# Sheet2.net
KiCad netlist of a schematic drawn in Altium Designer
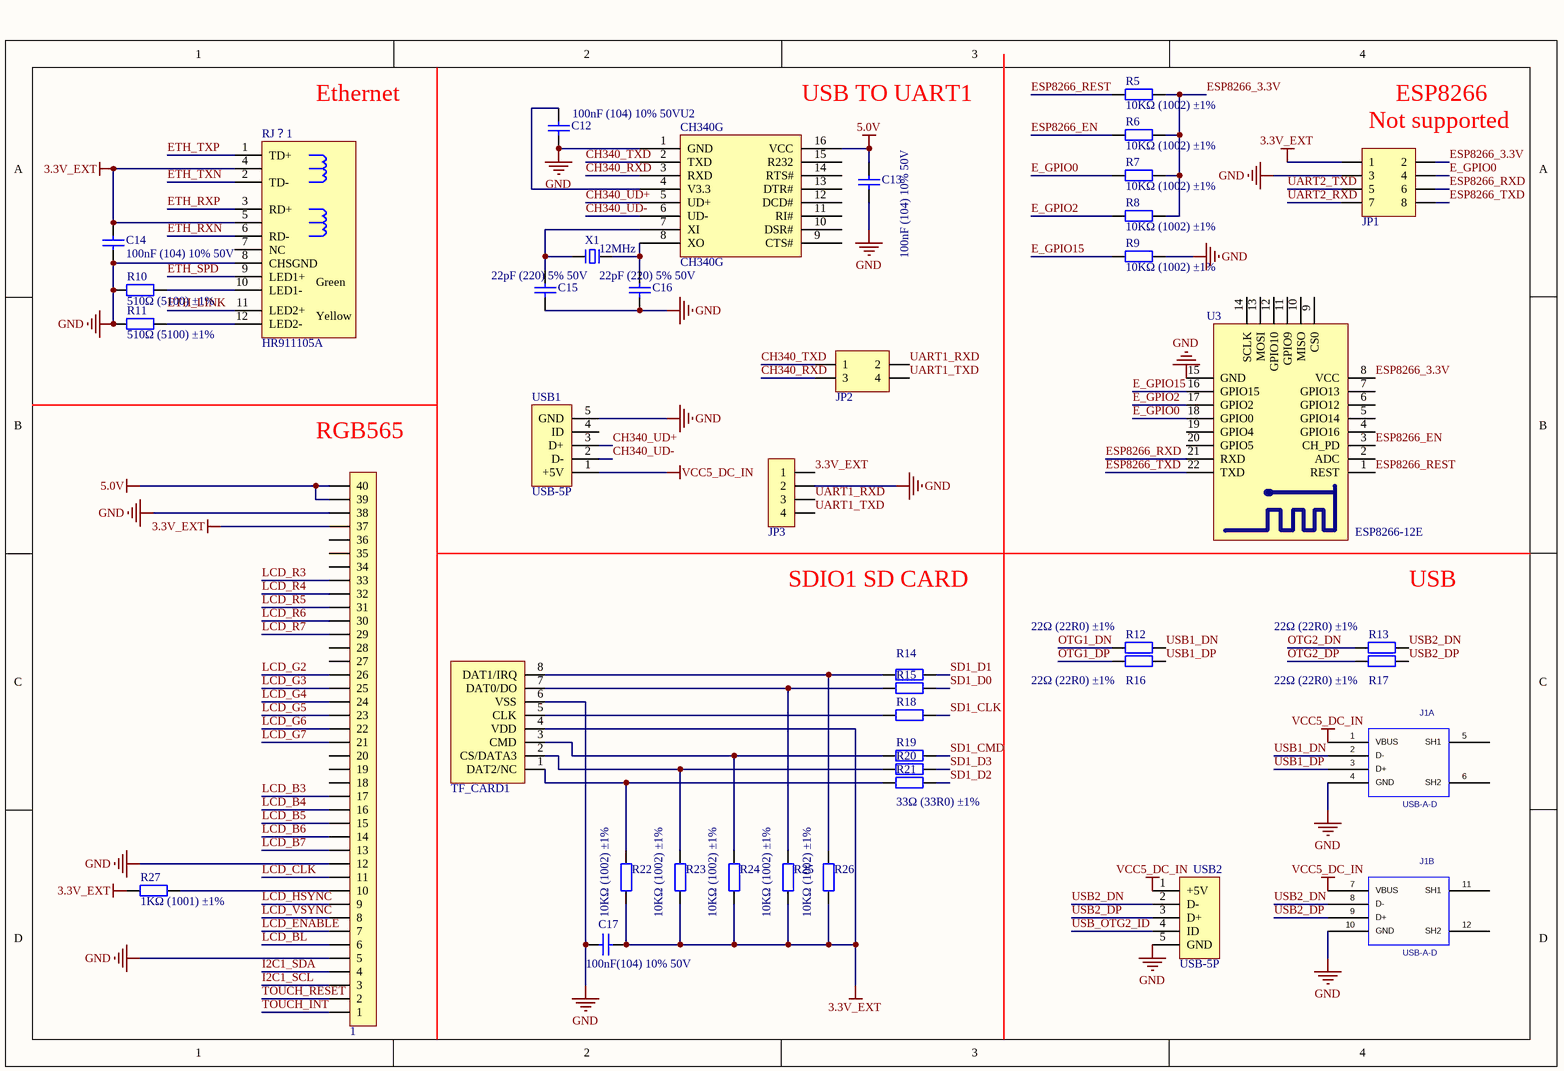
[diagram p0: Sheet2.SchDoc]

(export (version "E")
  (design (tool "Eeschema 10.0.6"))
  (components
    (comp (ref "1")
      (value "FPC1.0-40P")
      (footprint "FPC0.5 2H-S-W-40P")
      (description "FPC连接器")
      (fields (field (name "版权归属") "源创客"))
      (libsource (lib "FPC连接器") (part "FPC-40P"))
    )
    (comp (ref "C12")
      (value "100nF (104) 10% 50V")
      (footprint "0603_C")
      (description "贴片电容")
      (libsource (lib "Cap") (part "0603 100nF (104) 10% 50V"))
    )
    (comp (ref "C13")
      (value "100nF (104) 10% 50V")
      (footprint "0603_C")
      (description "贴片电容")
      (libsource (lib "Cap") (part "0603 100nF (104) 10% 50V"))
    )
    (comp (ref "C14")
      (value "100nF (104) 10% 50V")
      (footprint "0603_C")
      (description "贴片电容")
      (libsource (lib "Cap") (part "0603 100nF (104) 10% 50V"))
    )
    (comp (ref "C15")
      (value "22pF (220) 5% 50V")
      (footprint "0603_C")
      (description "贴片电容")
      (libsource (lib "Cap") (part "0805 22pF (220) 5% 50V"))
    )
    (comp (ref "C16")
      (value "22pF (220) 5% 50V")
      (footprint "0603_C")
      (description "贴片电容")
      (libsource (lib "Cap") (part "0805 22pF (220) 5% 50V"))
    )
    (comp (ref "C17")
      (value "100nF(104) 10% 50V")
      (footprint "0805_C")
      (description "贴片电容")
      (libsource (lib "Cap") (part "0805 100nF(104) 10% 50V"))
    )
    (comp (ref "J1")
      (value "USB-A-D")
      (footprint "USB-A-D")
      (fields (field (name "Comment") "USB-A-D_0"))
      (libsource (lib "IMXRT1052_MB_PRO") (part "USB-A-D_0"))
    )
    (comp (ref "JP1")
      (value "Header 4X2")
      (footprint "HDR-4X2")
      (description "4*2P接插件")
      (fields (field (name "版权归属") "源创客"))
      (libsource (lib "接插件") (part "Header 4X2"))
    )
    (comp (ref "JP2")
      (value "Header2X2")
      (footprint "HDR-2X2")
      (description "2*2P接插件")
      (fields (field (name "版权归属") "源创客"))
      (libsource (lib "接插件") (part "Header 2X2"))
    )
    (comp (ref "JP3")
      (value "HDR-1X4")
      (footprint "HDR-1X4_M")
      (description "4P接插件")
      (fields (field (name "版权归属") "源创客"))
      (libsource (lib "接插件") (part "Header 4"))
    )
    (comp (ref "R5")
      (value "10KΩ (1002) ±1%")
      (footprint "0603_R")
      (description "贴片电阻")
      (libsource (lib "") (part "0603 10KΩ (1002) 1%_1"))
    )
    (comp (ref "R6")
      (value "10KΩ (1002) ±1%")
      (footprint "0603_R")
      (description "贴片电阻")
      (libsource (lib "") (part "0603 10KΩ (1002) 1%_1"))
    )
    (comp (ref "R7")
      (value "10KΩ (1002) ±1%")
      (footprint "0603_R")
      (description "贴片电阻")
      (libsource (lib "") (part "0603 10KΩ (1002) 1%_1"))
    )
    (comp (ref "R8")
      (value "10KΩ (1002) ±1%")
      (footprint "0603_R")
      (description "贴片电阻")
      (libsource (lib "") (part "0603 10KΩ (1002) 1%_1"))
    )
    (comp (ref "R9")
      (value "10KΩ (1002) ±1%")
      (footprint "0603_R")
      (description "贴片电阻")
      (libsource (lib "RES") (part "0603 10KΩ (1002) 1%"))
    )
    (comp (ref "R10")
      (value "510Ω (5100) ±1%")
      (footprint "0603_R")
      (description "贴片电阻")
      (libsource (lib "RES") (part "0603 510Ω (5100) 1%"))
    )
    (comp (ref "R11")
      (value "510Ω (5100) ±1%")
      (footprint "0603_R")
      (description "贴片电阻")
      (libsource (lib "RES") (part "0603 510Ω (5100) 1%"))
    )
    (comp (ref "R12")
      (value "22Ω (22R0) ±1%")
      (footprint "0603_R")
      (description "贴片电阻")
      (libsource (lib "RES") (part "0603 22Ω (22R0) 1%"))
    )
    (comp (ref "R13")
      (value "22Ω (22R0) ±1%")
      (footprint "0603_R")
      (description "贴片电阻")
      (libsource (lib "RES") (part "0603 22Ω (22R0) 1%"))
    )
    (comp (ref "R14")
      (value "33Ω (33R0) ±1%")
      (footprint "0603_R")
      (description "贴片电阻")
      (libsource (lib "RES") (part "0603 33Ω (33R0) 1%"))
    )
    (comp (ref "R15")
      (value "33Ω (33R0) ±1%")
      (footprint "0603_R")
      (description "贴片电阻")
      (libsource (lib "RES") (part "0603 33Ω (33R0) 1%"))
    )
    (comp (ref "R16")
      (value "22Ω (22R0) ±1%")
      (footprint "0603_R")
      (description "贴片电阻")
      (libsource (lib "RES") (part "0603 22Ω (22R0) 1%"))
    )
    (comp (ref "R17")
      (value "22Ω (22R0) ±1%")
      (footprint "0603_R")
      (description "贴片电阻")
      (libsource (lib "RES") (part "0603 22Ω (22R0) 1%"))
    )
    (comp (ref "R18")
      (value "33Ω (33R0) ±1%")
      (footprint "0603_R")
      (description "贴片电阻")
      (libsource (lib "RES") (part "0603 33Ω (33R0) 1%"))
    )
    (comp (ref "R19")
      (value "33Ω (33R0) ±1%")
      (footprint "0603_R")
      (description "贴片电阻")
      (libsource (lib "RES") (part "0603 33Ω (33R0) 1%"))
    )
    (comp (ref "R20")
      (value "33Ω (33R0) ±1%")
      (footprint "0603_R")
      (description "贴片电阻")
      (libsource (lib "RES") (part "0603 33Ω (33R0) 1%"))
    )
    (comp (ref "R21")
      (value "33Ω (33R0) ±1%")
      (footprint "0603_R")
      (description "贴片电阻")
      (libsource (lib "RES") (part "0603 33Ω (33R0) 1%"))
    )
    (comp (ref "R22")
      (value "10KΩ (1002) ±1%")
      (footprint "0603_R")
      (description "贴片电阻")
      (libsource (lib "") (part "0603 10KΩ (1002) 1%_2"))
    )
    (comp (ref "R23")
      (value "10KΩ (1002) ±1%")
      (footprint "0603_R")
      (description "贴片电阻")
      (libsource (lib "") (part "0603 10KΩ (1002) 1%_2"))
    )
    (comp (ref "R24")
      (value "10KΩ (1002) ±1%")
      (footprint "0603_R")
      (description "贴片电阻")
      (libsource (lib "") (part "0603 10KΩ (1002) 1%_2"))
    )
    (comp (ref "R25")
      (value "10KΩ (1002) ±1%")
      (footprint "0603_R")
      (description "贴片电阻")
      (libsource (lib "") (part "0603 10KΩ (1002) 1%_2"))
    )
    (comp (ref "R26")
      (value "10KΩ (1002) ±1%")
      (footprint "0603_R")
      (description "贴片电阻")
      (libsource (lib "") (part "0603 10KΩ (1002) 1%_2"))
    )
    (comp (ref "R27")
      (value "1KΩ (1001) ±1%")
      (footprint "0603_R")
      (description "贴片电阻")
      (libsource (lib "RES") (part "0603 1KΩ (1001) 1%"))
    )
    (comp (ref "RJ？1")
      (value "HR911105A")
      (footprint "RJ-45A12")
      (description "带灯以太网接口")
      (fields (field (name "版权归属") "源创客"))
      (libsource (lib "接口类") (part "HR911105A"))
    )
    (comp (ref "TF_CARD1")
      (value "SD-MICRO-TF")
      (footprint "SD-MICRO-TF")
      (description "SD,MICRO,TF")
      (libsource (lib "Pandora_STM32L4_Board_V2.4") (part "SD-MICRO-TF"))
    )
    (comp (ref "U2")
      (value "CH340G")
      (footprint "SOIC-16_150mil")
      (description "USB")
      (libsource (lib "IC") (part "CH340G_[C14267]"))
    )
    (comp (ref "U3")
      (value "ESP8266-12E")
      (footprint "ESP_12E")
      (description "串口 WIFI模块，ESP-12E")
      (fields (field (name "版权归属") "源创客"))
      (libsource (lib "模块") (part "ESP8266-12E"))
    )
    (comp (ref "USB1")
      (value "USB-5P")
      (footprint "USB-MINI-A")
      (description "微型USB母座")
      (fields (field (name "版权归属") "源创客"))
      (libsource (lib "") (part "USB-5P_1"))
    )
    (comp (ref "USB2")
      (value "USB-5P")
      (footprint "USB-MINI-A")
      (description "微型USB母座")
      (fields (field (name "版权归属") "源创客"))
      (libsource (lib "接口类") (part "USB-5P"))
    )
    (comp (ref "X1")
      (value "12MHz")
      (footprint "XTAL-49S DIP")
      (description "2脚晶振")
      (fields (field (name "版权归属") "源创客"))
      (libsource (lib "保险丝-晶振") (part "XTAL-2"))
    )
  )
  (nets
    (net (code "1") (name "/CH340_RXD") (class "Default")
      (node (ref "JP2") (pin "3") (pinfunction "3_3") (pintype "passive"))
      (node (ref "U2") (pin "3") (pinfunction "RXD_3") (pintype "passive"))
    )
    (net (code "2") (name "/CH340_TXD") (class "Default")
      (node (ref "JP2") (pin "1") (pinfunction "1_1") (pintype "passive"))
      (node (ref "U2") (pin "2") (pinfunction "TXD_2") (pintype "passive"))
    )
    (net (code "3") (name "/CH340_UD+") (class "Default")
      (node (ref "U2") (pin "5") (pinfunction "UD+_5") (pintype "passive"))
      (node (ref "USB1") (pin "3") (pinfunction "D+_3") (pintype "passive"))
    )
    (net (code "4") (name "/CH340_UD-") (class "Default")
      (node (ref "U2") (pin "6") (pinfunction "UD-_6") (pintype "passive"))
      (node (ref "USB1") (pin "2") (pinfunction "D-_2") (pintype "passive"))
    )
    (net (code "5") (name "/ESP8266_3.3V") (class "Default")
      (node (ref "JP1") (pin "2") (pinfunction "2_2") (pintype "passive"))
      (node (ref "R5") (pin "2") (pinfunction "2_2") (pintype "passive"))
      (node (ref "R6") (pin "2") (pinfunction "2_2") (pintype "passive"))
      (node (ref "R7") (pin "2") (pinfunction "2_2") (pintype "passive"))
      (node (ref "R8") (pin "2") (pinfunction "2_2") (pintype "passive"))
      (node (ref "U3") (pin "8") (pinfunction "VCC_8") (pintype "passive"))
    )
    (net (code "6") (name "/ESP8266_EN") (class "Default")
      (node (ref "R6") (pin "1") (pinfunction "1_1") (pintype "passive"))
      (node (ref "U3") (pin "3") (pinfunction "CH_PD_3") (pintype "passive"))
    )
    (net (code "7") (name "/ESP8266_REST") (class "Default")
      (node (ref "R5") (pin "1") (pinfunction "1_1") (pintype "passive"))
      (node (ref "U3") (pin "1") (pinfunction "REST_1") (pintype "passive"))
    )
    (net (code "8") (name "/ESP8266_RXD") (class "Default")
      (node (ref "JP1") (pin "6") (pinfunction "6_6") (pintype "passive"))
      (node (ref "U3") (pin "21") (pinfunction "RXD_21") (pintype "passive"))
    )
    (net (code "9") (name "/ESP8266_TXD") (class "Default")
      (node (ref "JP1") (pin "8") (pinfunction "8_8") (pintype "passive"))
      (node (ref "U3") (pin "22") (pinfunction "TXD_22") (pintype "passive"))
    )
    (net (code "10") (name "/ETH_LINK") (class "Default")
      (node (ref "RJ？1") (pin "11") (pinfunction "LED2+_11") (pintype "passive"))
    )
    (net (code "11") (name "/ETH_RXN") (class "Default")
      (node (ref "RJ？1") (pin "6") (pinfunction "RD-_6") (pintype "passive"))
    )
    (net (code "12") (name "/ETH_RXP") (class "Default")
      (node (ref "RJ？1") (pin "3") (pinfunction "RD+_3") (pintype "passive"))
    )
    (net (code "13") (name "/ETH_SPD") (class "Default")
      (node (ref "RJ？1") (pin "9") (pinfunction "LED1+_9") (pintype "passive"))
    )
    (net (code "14") (name "/ETH_TXN") (class "Default")
      (node (ref "RJ？1") (pin "2") (pinfunction "TD-_2") (pintype "passive"))
    )
    (net (code "15") (name "/ETH_TXP") (class "Default")
      (node (ref "RJ？1") (pin "1") (pinfunction "TD+_1") (pintype "passive"))
    )
    (net (code "16") (name "/E_GPIO0") (class "Default")
      (node (ref "JP1") (pin "4") (pinfunction "4_4") (pintype "passive"))
      (node (ref "R7") (pin "1") (pinfunction "1_1") (pintype "passive"))
      (node (ref "U3") (pin "18") (pinfunction "GPIO0_18") (pintype "passive"))
    )
    (net (code "17") (name "/E_GPIO2") (class "Default")
      (node (ref "R8") (pin "1") (pinfunction "1_1") (pintype "passive"))
      (node (ref "U3") (pin "17") (pinfunction "GPIO2_17") (pintype "passive"))
    )
    (net (code "18") (name "/E_GPIO15") (class "Default")
      (node (ref "R9") (pin "2") (pinfunction "2_2") (pintype "passive"))
      (node (ref "U3") (pin "16") (pinfunction "GPIO15_16") (pintype "passive"))
    )
    (net (code "19") (name "/I2C1_SCL") (class "Default")
      (node (ref "1") (pin "3") (pinfunction "3_3") (pintype "passive"))
    )
    (net (code "20") (name "/I2C1_SDA") (class "Default")
      (node (ref "1") (pin "4") (pinfunction "4_4") (pintype "passive"))
    )
    (net (code "21") (name "/LCD_B3") (class "Default")
      (node (ref "1") (pin "17") (pinfunction "17_17") (pintype "passive"))
    )
    (net (code "22") (name "/LCD_B4") (class "Default")
      (node (ref "1") (pin "16") (pinfunction "16_16") (pintype "passive"))
    )
    (net (code "23") (name "/LCD_B5") (class "Default")
      (node (ref "1") (pin "15") (pinfunction "15_15") (pintype "passive"))
    )
    (net (code "24") (name "/LCD_B6") (class "Default")
      (node (ref "1") (pin "14") (pinfunction "14_14") (pintype "passive"))
    )
    (net (code "25") (name "/LCD_B7") (class "Default")
      (node (ref "1") (pin "13") (pinfunction "13_13") (pintype "passive"))
    )
    (net (code "26") (name "/LCD_BL") (class "Default")
      (node (ref "1") (pin "6") (pinfunction "6_6") (pintype "passive"))
    )
    (net (code "27") (name "/LCD_CLK") (class "Default")
      (node (ref "1") (pin "11") (pinfunction "11_11") (pintype "passive"))
    )
    (net (code "28") (name "/LCD_ENABLE") (class "Default")
      (node (ref "1") (pin "7") (pinfunction "7_7") (pintype "passive"))
    )
    (net (code "29") (name "/LCD_G2") (class "Default")
      (node (ref "1") (pin "26") (pinfunction "26_26") (pintype "passive"))
    )
    (net (code "30") (name "/LCD_G3") (class "Default")
      (node (ref "1") (pin "25") (pinfunction "25_25") (pintype "passive"))
    )
    (net (code "31") (name "/LCD_G4") (class "Default")
      (node (ref "1") (pin "24") (pinfunction "24_24") (pintype "passive"))
    )
    (net (code "32") (name "/LCD_G5") (class "Default")
      (node (ref "1") (pin "23") (pinfunction "23_23") (pintype "passive"))
    )
    (net (code "33") (name "/LCD_G6") (class "Default")
      (node (ref "1") (pin "22") (pinfunction "22_22") (pintype "passive"))
    )
    (net (code "34") (name "/LCD_G7") (class "Default")
      (node (ref "1") (pin "21") (pinfunction "21_21") (pintype "passive"))
    )
    (net (code "35") (name "/LCD_HSYNC") (class "Default")
      (node (ref "1") (pin "9") (pinfunction "9_9") (pintype "passive"))
    )
    (net (code "36") (name "/LCD_R3") (class "Default")
      (node (ref "1") (pin "33") (pinfunction "33_33") (pintype "passive"))
    )
    (net (code "37") (name "/LCD_R4") (class "Default")
      (node (ref "1") (pin "32") (pinfunction "32_32") (pintype "passive"))
    )
    (net (code "38") (name "/LCD_R5") (class "Default")
      (node (ref "1") (pin "31") (pinfunction "31_31") (pintype "passive"))
    )
    (net (code "39") (name "/LCD_R6") (class "Default")
      (node (ref "1") (pin "30") (pinfunction "30_30") (pintype "passive"))
    )
    (net (code "40") (name "/LCD_R7") (class "Default")
      (node (ref "1") (pin "29") (pinfunction "29_29") (pintype "passive"))
    )
    (net (code "41") (name "/LCD_VSYNC") (class "Default")
      (node (ref "1") (pin "8") (pinfunction "8_8") (pintype "passive"))
    )
    (net (code "42") (name "/OTG1_DN") (class "Default")
      (node (ref "R12") (pin "1") (pinfunction "1_1") (pintype "passive"))
    )
    (net (code "43") (name "/OTG1_DP") (class "Default")
      (node (ref "R16") (pin "1") (pinfunction "1_1") (pintype "passive"))
    )
    (net (code "44") (name "/OTG2_DN") (class "Default")
      (node (ref "R13") (pin "1") (pinfunction "1_1") (pintype "passive"))
    )
    (net (code "45") (name "/OTG2_DP") (class "Default")
      (node (ref "R17") (pin "1") (pinfunction "1_1") (pintype "passive"))
    )
    (net (code "46") (name "/SD1_CLK") (class "Default")
      (node (ref "R18") (pin "2") (pinfunction "2_2") (pintype "passive"))
    )
    (net (code "47") (name "/SD1_CMD") (class "Default")
      (node (ref "R19") (pin "2") (pinfunction "2_2") (pintype "passive"))
    )
    (net (code "48") (name "/SD1_D0") (class "Default")
      (node (ref "R15") (pin "2") (pinfunction "2_2") (pintype "passive"))
    )
    (net (code "49") (name "/SD1_D1") (class "Default")
      (node (ref "R14") (pin "2") (pinfunction "2_2") (pintype "passive"))
    )
    (net (code "50") (name "/SD1_D2") (class "Default")
      (node (ref "R21") (pin "2") (pinfunction "2_2") (pintype "passive"))
    )
    (net (code "51") (name "/SD1_D3") (class "Default")
      (node (ref "R20") (pin "2") (pinfunction "2_2") (pintype "passive"))
    )
    (net (code "52") (name "/TOUCH_INT") (class "Default")
      (node (ref "1") (pin "1") (pinfunction "1_1") (pintype "passive"))
    )
    (net (code "53") (name "/TOUCH_RESET") (class "Default")
      (node (ref "1") (pin "2") (pinfunction "2_2") (pintype "passive"))
    )
    (net (code "54") (name "/UART1_RXD") (class "Default")
      (node (ref "JP2") (pin "2") (pinfunction "2_2") (pintype "passive"))
      (node (ref "JP3") (pin "3") (pinfunction "3_3") (pintype "passive"))
    )
    (net (code "55") (name "/UART1_TXD") (class "Default")
      (node (ref "JP2") (pin "4") (pinfunction "4_4") (pintype "passive"))
      (node (ref "JP3") (pin "4") (pinfunction "4_4") (pintype "passive"))
    )
    (net (code "56") (name "/UART2_RXD") (class "Default")
      (node (ref "JP1") (pin "7") (pinfunction "7_7") (pintype "passive"))
    )
    (net (code "57") (name "/UART2_TXD") (class "Default")
      (node (ref "JP1") (pin "5") (pinfunction "5_5") (pintype "passive"))
    )
    (net (code "58") (name "/USB1_DN") (class "Default")
      (node (ref "J1") (pin "2") (pinfunction "D-_2") (pintype "passive"))
      (node (ref "R12") (pin "2") (pinfunction "2_2") (pintype "passive"))
    )
    (net (code "59") (name "/USB1_DP") (class "Default")
      (node (ref "J1") (pin "3") (pinfunction "D+_3") (pintype "passive"))
      (node (ref "R16") (pin "2") (pinfunction "2_2") (pintype "passive"))
    )
    (net (code "60") (name "/USB2_DN") (class "Default")
      (node (ref "J1") (pin "8") (pinfunction "D-_8") (pintype "passive"))
      (node (ref "R13") (pin "2") (pinfunction "2_2") (pintype "passive"))
      (node (ref "USB2") (pin "2") (pinfunction "D-_2") (pintype "passive"))
    )
    (net (code "61") (name "/USB2_DP") (class "Default")
      (node (ref "J1") (pin "9") (pinfunction "D+_9") (pintype "passive"))
      (node (ref "R17") (pin "2") (pinfunction "2_2") (pintype "passive"))
      (node (ref "USB2") (pin "3") (pinfunction "D+_3") (pintype "passive"))
    )
    (net (code "62") (name "/USB_OTG2_ID") (class "Default")
      (node (ref "USB2") (pin "4") (pinfunction "ID_4") (pintype "passive"))
    )
    (net (code "63") (name "3.3V_EXT") (class "Default")
      (node (ref "1") (pin "37") (pinfunction "37_37") (pintype "passive"))
      (node (ref "C14") (pin "2") (pinfunction "2_2") (pintype "passive"))
      (node (ref "C17") (pin "1") (pinfunction "1_1") (pintype "passive"))
      (node (ref "JP1") (pin "1") (pinfunction "1_1") (pintype "passive"))
      (node (ref "JP3") (pin "1") (pinfunction "1_1") (pintype "passive"))
      (node (ref "R22") (pin "1") (pinfunction "1_1") (pintype "passive"))
      (node (ref "R23") (pin "1") (pinfunction "1_1") (pintype "passive"))
      (node (ref "R24") (pin "1") (pinfunction "1_1") (pintype "passive"))
      (node (ref "R25") (pin "1") (pinfunction "1_1") (pintype "passive"))
      (node (ref "R26") (pin "1") (pinfunction "1_1") (pintype "passive"))
      (node (ref "R27") (pin "2") (pinfunction "2_2") (pintype "passive"))
      (node (ref "RJ？1") (pin "4") (pintype "passive"))
      (node (ref "RJ？1") (pin "5") (pintype "passive"))
      (node (ref "TF_CARD1") (pin "4") (pinfunction "VDD_4") (pintype "passive"))
    )
    (net (code "64") (name "5.0V") (class "Default")
      (node (ref "1") (pin "39") (pinfunction "39_39") (pintype "passive"))
      (node (ref "1") (pin "40") (pinfunction "40_40") (pintype "passive"))
      (node (ref "C13") (pin "1") (pinfunction "1_1") (pintype "passive"))
      (node (ref "U2") (pin "16") (pinfunction "VCC_16") (pintype "passive"))
    )
    (net (code "65") (name "GND") (class "Default")
      (node (ref "1") (pin "12") (pinfunction "12_12") (pintype "passive"))
      (node (ref "1") (pin "38") (pinfunction "38_38") (pintype "passive"))
      (node (ref "1") (pin "5") (pinfunction "5_5") (pintype "passive"))
      (node (ref "C12") (pin "1") (pinfunction "1_1") (pintype "passive"))
      (node (ref "C13") (pin "2") (pinfunction "2_2") (pintype "passive"))
      (node (ref "C14") (pin "1") (pinfunction "1_1") (pintype "passive"))
      (node (ref "C15") (pin "2") (pinfunction "2_2") (pintype "passive"))
      (node (ref "C16") (pin "2") (pinfunction "2_2") (pintype "passive"))
      (node (ref "C17") (pin "2") (pinfunction "2_2") (pintype "passive"))
      (node (ref "J1") (pin "10") (pinfunction "GND_10") (pintype "passive"))
      (node (ref "J1") (pin "4") (pinfunction "GND_4") (pintype "passive"))
      (node (ref "JP1") (pin "3") (pinfunction "3_3") (pintype "passive"))
      (node (ref "JP3") (pin "2") (pinfunction "2_2") (pintype "passive"))
      (node (ref "R10") (pin "1") (pinfunction "1_1") (pintype "passive"))
      (node (ref "R11") (pin "1") (pinfunction "1_1") (pintype "passive"))
      (node (ref "R9") (pin "1") (pinfunction "1_1") (pintype "passive"))
      (node (ref "RJ？1") (pin "8") (pinfunction "CHSGND_8") (pintype "passive"))
      (node (ref "TF_CARD1") (pin "6") (pinfunction "VSS_6") (pintype "passive"))
      (node (ref "U2") (pin "1") (pinfunction "GND_1") (pintype "passive"))
      (node (ref "U3") (pin "15") (pinfunction "GND_15") (pintype "passive"))
      (node (ref "USB1") (pin "5") (pinfunction "GND_5") (pintype "passive"))
      (node (ref "USB2") (pin "5") (pinfunction "GND_5") (pintype "passive"))
    )
    (net (code "66") (name "Net-(1-Pad10)") (class "Default")
      (node (ref "1") (pin "10") (pinfunction "10_10") (pintype "passive"))
      (node (ref "R27") (pin "1") (pinfunction "1_1") (pintype "passive"))
    )
    (net (code "67") (name "Net-(RJ？1-LED1-)") (class "Default")
      (node (ref "R10") (pin "2") (pinfunction "2_2") (pintype "passive"))
      (node (ref "RJ？1") (pin "10") (pinfunction "LED1-_10") (pintype "passive"))
    )
    (net (code "68") (name "Net-(RJ？1-LED2-)") (class "Default")
      (node (ref "R11") (pin "2") (pinfunction "2_2") (pintype "passive"))
      (node (ref "RJ？1") (pin "12") (pinfunction "LED2-_12") (pintype "passive"))
    )
    (net (code "69") (name "Net-(TF_CARD1-CLK)") (class "Default")
      (node (ref "R18") (pin "1") (pinfunction "1_1") (pintype "passive"))
      (node (ref "TF_CARD1") (pin "5") (pinfunction "CLK_5") (pintype "passive"))
    )
    (net (code "70") (name "Net-(TF_CARD1-CMD)") (class "Default")
      (node (ref "R19") (pin "1") (pinfunction "1_1") (pintype "passive"))
      (node (ref "R24") (pin "2") (pinfunction "2_2") (pintype "passive"))
      (node (ref "TF_CARD1") (pin "3") (pinfunction "CMD_3") (pintype "passive"))
    )
    (net (code "71") (name "Net-(TF_CARD1-CS{slash}DATA3)") (class "Default")
      (node (ref "R20") (pin "1") (pinfunction "1_1") (pintype "passive"))
      (node (ref "R23") (pin "2") (pinfunction "2_2") (pintype "passive"))
      (node (ref "TF_CARD1") (pin "2") (pinfunction "CS/DATA3_2") (pintype "passive"))
    )
    (net (code "72") (name "Net-(TF_CARD1-DAT0{slash}DO)") (class "Default")
      (node (ref "R15") (pin "1") (pinfunction "1_1") (pintype "passive"))
      (node (ref "R25") (pin "2") (pinfunction "2_2") (pintype "passive"))
      (node (ref "TF_CARD1") (pin "7") (pinfunction "DAT0/DO_7") (pintype "passive"))
    )
    (net (code "73") (name "Net-(TF_CARD1-DAT1{slash}IRQ)") (class "Default")
      (node (ref "R14") (pin "1") (pinfunction "1_1") (pintype "passive"))
      (node (ref "R26") (pin "2") (pinfunction "2_2") (pintype "passive"))
      (node (ref "TF_CARD1") (pin "8") (pinfunction "DAT1/IRQ_8") (pintype "passive"))
    )
    (net (code "74") (name "Net-(TF_CARD1-DAT2{slash}NC)") (class "Default")
      (node (ref "R21") (pin "1") (pinfunction "1_1") (pintype "passive"))
      (node (ref "R22") (pin "2") (pinfunction "2_2") (pintype "passive"))
      (node (ref "TF_CARD1") (pin "1") (pinfunction "DAT2/NC_1") (pintype "passive"))
    )
    (net (code "75") (name "Net-(U2-V3.3)") (class "Default")
      (node (ref "C12") (pin "2") (pinfunction "2_2") (pintype "passive"))
      (node (ref "U2") (pin "4") (pinfunction "V3.3_4") (pintype "passive"))
    )
    (net (code "76") (name "Net-(U2-XI)") (class "Default")
      (node (ref "C15") (pin "1") (pinfunction "1_1") (pintype "passive"))
      (node (ref "U2") (pin "7") (pinfunction "XI_7") (pintype "passive"))
      (node (ref "X1") (pin "1") (pinfunction "1_1") (pintype "passive"))
    )
    (net (code "77") (name "Net-(U2-XO)") (class "Default")
      (node (ref "C16") (pin "1") (pinfunction "1_1") (pintype "passive"))
      (node (ref "U2") (pin "8") (pinfunction "XO_8") (pintype "passive"))
      (node (ref "X1") (pin "2") (pinfunction "2_2") (pintype "passive"))
    )
    (net (code "78") (name "VCC5_DC_IN") (class "Default")
      (node (ref "J1") (pin "1") (pinfunction "VBUS_1") (pintype "passive"))
      (node (ref "J1") (pin "7") (pinfunction "VBUS_7") (pintype "passive"))
      (node (ref "USB1") (pin "1") (pinfunction "+5V_1") (pintype "passive"))
      (node (ref "USB2") (pin "1") (pinfunction "+5V_1") (pintype "passive"))
    )
    (net (code "79") (name "unconnected-(1-Pad18)") (class "Default")
      (node (ref "1") (pin "18") (pinfunction "18_18") (pintype "passive"))
    )
    (net (code "80") (name "unconnected-(1-Pad19)") (class "Default")
      (node (ref "1") (pin "19") (pinfunction "19_19") (pintype "passive"))
    )
    (net (code "81") (name "unconnected-(1-Pad20)") (class "Default")
      (node (ref "1") (pin "20") (pinfunction "20_20") (pintype "passive"))
    )
    (net (code "82") (name "unconnected-(1-Pad27)") (class "Default")
      (node (ref "1") (pin "27") (pinfunction "27_27") (pintype "passive"))
    )
    (net (code "83") (name "unconnected-(1-Pad28)") (class "Default")
      (node (ref "1") (pin "28") (pinfunction "28_28") (pintype "passive"))
    )
    (net (code "84") (name "unconnected-(1-Pad34)") (class "Default")
      (node (ref "1") (pin "34") (pinfunction "34_34") (pintype "passive"))
    )
    (net (code "85") (name "unconnected-(1-Pad35)") (class "Default")
      (node (ref "1") (pin "35") (pinfunction "35_35") (pintype "passive"))
    )
    (net (code "86") (name "unconnected-(1-Pad36)") (class "Default")
      (node (ref "1") (pin "36") (pinfunction "36_36") (pintype "passive"))
    )
    (net (code "87") (name "unconnected-(J1A-SH1-Pad5)") (class "Default")
      (node (ref "J1") (pin "5") (pinfunction "SH1_5") (pintype "passive"))
    )
    (net (code "88") (name "unconnected-(J1A-SH2-Pad6)") (class "Default")
      (node (ref "J1") (pin "6") (pinfunction "SH2_6") (pintype "passive"))
    )
    (net (code "89") (name "unconnected-(J1B-SH1-Pad11)") (class "Default")
      (node (ref "J1") (pin "11") (pinfunction "SH1_11") (pintype "passive"))
    )
    (net (code "90") (name "unconnected-(J1B-SH2-Pad12)") (class "Default")
      (node (ref "J1") (pin "12") (pinfunction "SH2_12") (pintype "passive"))
    )
    (net (code "91") (name "unconnected-(RJ？1-NC-Pad7)") (class "Default")
      (node (ref "RJ？1") (pin "7") (pinfunction "NC_7") (pintype "passive"))
    )
    (net (code "92") (name "unconnected-(U2-CTS#-Pad9)") (class "Default")
      (node (ref "U2") (pin "9") (pinfunction "CTS#_9") (pintype "passive"))
    )
    (net (code "93") (name "unconnected-(U2-DCD#-Pad12)") (class "Default")
      (node (ref "U2") (pin "12") (pinfunction "DCD#_12") (pintype "passive"))
    )
    (net (code "94") (name "unconnected-(U2-DSR#-Pad10)") (class "Default")
      (node (ref "U2") (pin "10") (pinfunction "DSR#_10") (pintype "passive"))
    )
    (net (code "95") (name "unconnected-(U2-DTR#-Pad13)") (class "Default")
      (node (ref "U2") (pin "13") (pinfunction "DTR#_13") (pintype "passive"))
    )
    (net (code "96") (name "unconnected-(U2-R232-Pad15)") (class "Default")
      (node (ref "U2") (pin "15") (pinfunction "R232_15") (pintype "passive"))
    )
    (net (code "97") (name "unconnected-(U2-RI#-Pad11)") (class "Default")
      (node (ref "U2") (pin "11") (pinfunction "RI#_11") (pintype "passive"))
    )
    (net (code "98") (name "unconnected-(U2-RTS#-Pad14)") (class "Default")
      (node (ref "U2") (pin "14") (pinfunction "RTS#_14") (pintype "passive"))
    )
    (net (code "99") (name "unconnected-(U3-ADC-Pad2)") (class "Default")
      (node (ref "U3") (pin "2") (pinfunction "ADC_2") (pintype "passive"))
    )
    (net (code "100") (name "unconnected-(U3-CS0-Pad9)") (class "Default")
      (node (ref "U3") (pin "9") (pinfunction "CS0_9") (pintype "passive"))
    )
    (net (code "101") (name "unconnected-(U3-GPIO4-Pad19)") (class "Default")
      (node (ref "U3") (pin "19") (pinfunction "GPIO4_19") (pintype "passive"))
    )
    (net (code "102") (name "unconnected-(U3-GPIO5-Pad20)") (class "Default")
      (node (ref "U3") (pin "20") (pinfunction "GPIO5_20") (pintype "passive"))
    )
    (net (code "103") (name "unconnected-(U3-GPIO9-Pad11)") (class "Default")
      (node (ref "U3") (pin "11") (pinfunction "GPIO9_11") (pintype "passive"))
    )
    (net (code "104") (name "unconnected-(U3-GPIO10-Pad12)") (class "Default")
      (node (ref "U3") (pin "12") (pinfunction "GPIO10_12") (pintype "passive"))
    )
    (net (code "105") (name "unconnected-(U3-GPIO12-Pad6)") (class "Default")
      (node (ref "U3") (pin "6") (pinfunction "GPIO12_6") (pintype "passive"))
    )
    (net (code "106") (name "unconnected-(U3-GPIO13-Pad7)") (class "Default")
      (node (ref "U3") (pin "7") (pinfunction "GPIO13_7") (pintype "passive"))
    )
    (net (code "107") (name "unconnected-(U3-GPIO14-Pad5)") (class "Default")
      (node (ref "U3") (pin "5") (pinfunction "GPIO14_5") (pintype "passive"))
    )
    (net (code "108") (name "unconnected-(U3-GPIO16-Pad4)") (class "Default")
      (node (ref "U3") (pin "4") (pinfunction "GPIO16_4") (pintype "passive"))
    )
    (net (code "109") (name "unconnected-(U3-MISO-Pad10)") (class "Default")
      (node (ref "U3") (pin "10") (pinfunction "MISO_10") (pintype "passive"))
    )
    (net (code "110") (name "unconnected-(U3-MOSI-Pad13)") (class "Default")
      (node (ref "U3") (pin "13") (pinfunction "MOSI_13") (pintype "passive"))
    )
    (net (code "111") (name "unconnected-(U3-SCLK-Pad14)") (class "Default")
      (node (ref "U3") (pin "14") (pinfunction "SCLK_14") (pintype "passive"))
    )
    (net (code "112") (name "unconnected-(USB1-ID-Pad4)") (class "Default")
      (node (ref "USB1") (pin "4") (pinfunction "ID_4") (pintype "passive"))
    )
  )
)
